# ECU-CAN-Adapter_Verteilte_Systeme_27_09_.net
KiCad netlist of a schematic drawn in EAGLE
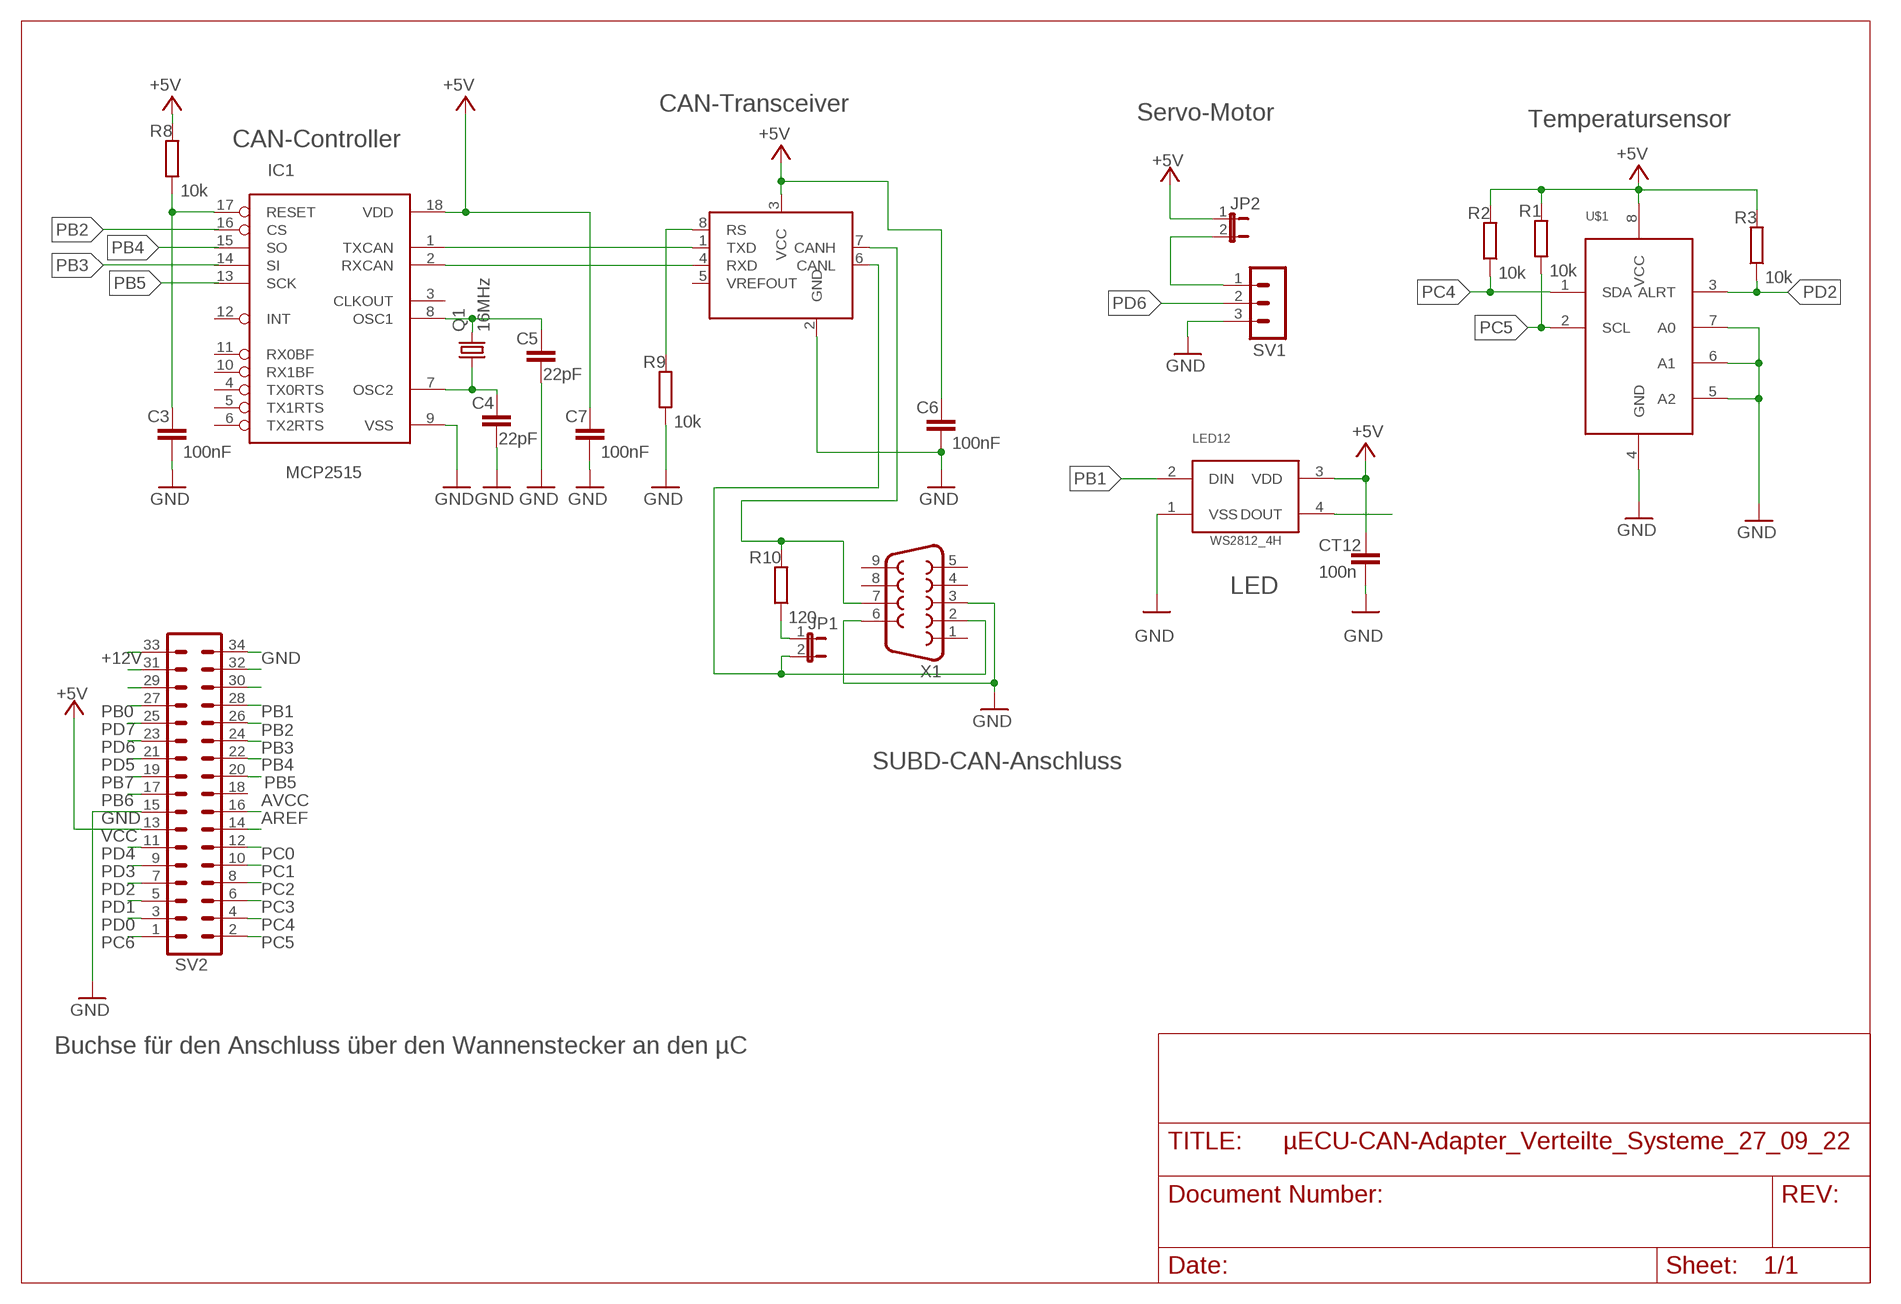
[diagram p0: schematic, sheet 1]

(export (version "E")
  (design (tool "Eeschema 10.0.6"))
  (components
    (comp (ref "C3")
      (value "100nF")
      (footprint "eagle-import:C0805K")
      (libsource (lib "eagle-import") (part "C-EUC0805K"))
    )
    (comp (ref "C4")
      (value "22pF")
      (footprint "eagle-import:C0805K")
      (libsource (lib "eagle-import") (part "C-EUC0805K"))
    )
    (comp (ref "C5")
      (value "22pF")
      (footprint "eagle-import:C0805K")
      (libsource (lib "eagle-import") (part "C-EUC0805K"))
    )
    (comp (ref "C6")
      (value "100nF")
      (footprint "eagle-import:C0805K")
      (libsource (lib "eagle-import") (part "C-EUC0805K"))
    )
    (comp (ref "C7")
      (value "100nF")
      (footprint "eagle-import:C0805K")
      (libsource (lib "eagle-import") (part "C-EUC0805K"))
    )
    (comp (ref "CT12")
      (value "100n")
      (footprint "eagle-import:C0805")
      (libsource (lib "eagle-import") (part "C-EUC0805"))
    )
    (comp (ref "IC1")
      (value "MCP2515")
      (footprint "eagle-import:SO-18DW")
      (libsource (lib "eagle-import") (part "MCP2515"))
    )
    (comp (ref "IC2")
      (value "PCA82C251")
      (footprint "eagle-import:SO8")
      (libsource (lib "eagle-import") (part "82C250SMDSMD"))
    )
    (comp (ref "JP1")
      (value "JP1E")
      (footprint "eagle-import:JP1")
      (libsource (lib "eagle-import") (part "JP1E"))
    )
    (comp (ref "JP2")
      (value "JP1E")
      (footprint "eagle-import:JP1")
      (libsource (lib "eagle-import") (part "JP1E"))
    )
    (comp (ref "LED12")
      (value "WS2812_4H")
      (footprint "eagle-import:WS2812_4")
      (libsource (lib "eagle-import") (part "WS2812_4H"))
    )
    (comp (ref "Q1")
      (value "16MHz")
      (footprint "eagle-import:HC49_S")
      (libsource (lib "eagle-import") (part "CRYSTALHC49S"))
    )
    (comp (ref "R1")
      (value "10k")
      (footprint "eagle-import:R0805")
      (libsource (lib "eagle-import") (part "R-EU_R0805"))
    )
    (comp (ref "R2")
      (value "10k")
      (footprint "eagle-import:R0805")
      (libsource (lib "eagle-import") (part "R-EU_R0805"))
    )
    (comp (ref "R3")
      (value "10k")
      (footprint "eagle-import:R0805")
      (libsource (lib "eagle-import") (part "R-EU_R0805"))
    )
    (comp (ref "R8")
      (value "10k")
      (footprint "eagle-import:R0805")
      (libsource (lib "eagle-import") (part "R-EU_R0805"))
    )
    (comp (ref "R9")
      (value "10k")
      (footprint "eagle-import:R0805")
      (libsource (lib "eagle-import") (part "R-EU_R0805"))
    )
    (comp (ref "R10")
      (value "120")
      (footprint "eagle-import:R0805")
      (libsource (lib "eagle-import") (part "R-EU_R0805"))
    )
    (comp (ref "SV1")
      (value "MA03-1")
      (footprint "eagle-import:MA03-1")
      (libsource (lib "eagle-import") (part "MA03-1"))
    )
    (comp (ref "SV2")
      (value "ML34")
      (footprint "eagle-import:ML34")
      (libsource (lib "eagle-import") (part "ML34"))
    )
    (comp (ref "U$1")
      (value "TMP75-SO8")
      (footprint "eagle-import:SO08")
      (libsource (lib "eagle-import") (part "TMP75-SO8"))
    )
    (comp (ref "X1")
      (value "F09HP")
      (footprint "eagle-import:F09HP")
      (libsource (lib "eagle-import") (part "F09HP"))
    )
  )
  (nets
    (net (code "1") (name "+5V") (class "Default")
      (node (ref "C6") (pin "1") (pinfunction "1_1") (pintype "passive"))
      (node (ref "C7") (pin "1") (pinfunction "1_1") (pintype "passive"))
      (node (ref "CT12") (pin "1") (pinfunction "1_1") (pintype "passive"))
      (node (ref "IC1") (pin "18") (pinfunction "VDD_18") (pintype "power_in"))
      (node (ref "IC2") (pin "3") (pinfunction "VCC_3") (pintype "power_in"))
      (node (ref "JP2") (pin "1") (pinfunction "1_1") (pintype "passive"))
      (node (ref "LED12") (pin "3") (pinfunction "VDD_3") (pintype "power_in"))
      (node (ref "R1") (pin "2") (pinfunction "2_2") (pintype "passive"))
      (node (ref "R2") (pin "2") (pinfunction "2_2") (pintype "passive"))
      (node (ref "R3") (pin "2") (pinfunction "2_2") (pintype "passive"))
      (node (ref "R8") (pin "2") (pinfunction "2_2") (pintype "passive"))
      (node (ref "SV2") (pin "13") (pinfunction "13_13") (pintype "passive"))
      (node (ref "U$1") (pin "8") (pinfunction "VCC_8") (pintype "power_in"))
    )
    (net (code "2") (name "/+12V") (class "Default")
      (node (ref "SV2") (pin "33") (pinfunction "33_33") (pintype "passive"))
    )
    (net (code "3") (name "/AREF") (class "Default")
      (node (ref "SV2") (pin "16") (pinfunction "16_16") (pintype "passive"))
    )
    (net (code "4") (name "/PB0") (class "Default")
      (node (ref "SV2") (pin "27") (pinfunction "27_27") (pintype "passive"))
    )
    (net (code "5") (name "/PB6") (class "Default")
      (node (ref "SV2") (pin "17") (pinfunction "17_17") (pintype "passive"))
    )
    (net (code "6") (name "/PB7") (class "Default")
      (node (ref "SV2") (pin "19") (pinfunction "19_19") (pintype "passive"))
    )
    (net (code "7") (name "/PC0") (class "Default")
      (node (ref "SV2") (pin "12") (pinfunction "12_12") (pintype "passive"))
    )
    (net (code "8") (name "/PC1") (class "Default")
      (node (ref "SV2") (pin "10") (pinfunction "10_10") (pintype "passive"))
    )
    (net (code "9") (name "/PC2") (class "Default")
      (node (ref "SV2") (pin "8") (pinfunction "8_8") (pintype "passive"))
    )
    (net (code "10") (name "/PC3") (class "Default")
      (node (ref "SV2") (pin "6") (pinfunction "6_6") (pintype "passive"))
    )
    (net (code "11") (name "/PC6") (class "Default")
      (node (ref "SV2") (pin "1") (pinfunction "1_1") (pintype "passive"))
    )
    (net (code "12") (name "/PD0") (class "Default")
      (node (ref "SV2") (pin "3") (pinfunction "3_3") (pintype "passive"))
    )
    (net (code "13") (name "/PD1") (class "Default")
      (node (ref "SV2") (pin "5") (pinfunction "5_5") (pintype "passive"))
    )
    (net (code "14") (name "/PD3") (class "Default")
      (node (ref "SV2") (pin "9") (pinfunction "9_9") (pintype "passive"))
    )
    (net (code "15") (name "/PD4") (class "Default")
      (node (ref "SV2") (pin "11") (pinfunction "11_11") (pintype "passive"))
    )
    (net (code "16") (name "/PD5") (class "Default")
      (node (ref "SV2") (pin "21") (pinfunction "21_21") (pintype "passive"))
    )
    (net (code "17") (name "/PD7") (class "Default")
      (node (ref "SV2") (pin "25") (pinfunction "25_25") (pintype "passive"))
    )
    (net (code "18") (name "GND") (class "Default")
      (node (ref "C3") (pin "2") (pinfunction "2_2") (pintype "passive"))
      (node (ref "C4") (pin "2") (pinfunction "2_2") (pintype "passive"))
      (node (ref "C5") (pin "2") (pinfunction "2_2") (pintype "passive"))
      (node (ref "C6") (pin "2") (pinfunction "2_2") (pintype "passive"))
      (node (ref "C7") (pin "2") (pinfunction "2_2") (pintype "passive"))
      (node (ref "CT12") (pin "2") (pinfunction "2_2") (pintype "passive"))
      (node (ref "IC1") (pin "9") (pinfunction "VSS_9") (pintype "power_in"))
      (node (ref "IC2") (pin "2") (pinfunction "GND_2") (pintype "power_in"))
      (node (ref "LED12") (pin "1") (pinfunction "VSS_1") (pintype "power_in"))
      (node (ref "R9") (pin "1") (pinfunction "1_1") (pintype "passive"))
      (node (ref "SV1") (pin "3") (pinfunction "3_3") (pintype "passive"))
      (node (ref "SV2") (pin "15") (pinfunction "15_15") (pintype "passive"))
      (node (ref "SV2") (pin "34") (pinfunction "34_34") (pintype "passive"))
      (node (ref "U$1") (pin "4") (pinfunction "GND_4") (pintype "power_in"))
      (node (ref "U$1") (pin "5") (pinfunction "A2_5") (pintype "input"))
      (node (ref "U$1") (pin "6") (pinfunction "A1_6") (pintype "input"))
      (node (ref "U$1") (pin "7") (pinfunction "A0_7") (pintype "input"))
      (node (ref "X1") (pin "3") (pinfunction "3_3") (pintype "passive"))
      (node (ref "X1") (pin "6") (pinfunction "6_6") (pintype "passive"))
    )
    (net (code "19") (name "Net-(IC1-OSC1)") (class "Default")
      (node (ref "C5") (pin "1") (pinfunction "1_1") (pintype "passive"))
      (node (ref "IC1") (pin "8") (pinfunction "OSC1_8") (pintype "input"))
      (node (ref "Q1") (pin "2") (pinfunction "2_2") (pintype "passive"))
    )
    (net (code "20") (name "Net-(IC1-OSC2)") (class "Default")
      (node (ref "C4") (pin "1") (pinfunction "1_1") (pintype "passive"))
      (node (ref "IC1") (pin "7") (pinfunction "OSC2_7") (pintype "input"))
      (node (ref "Q1") (pin "1") (pinfunction "1_1") (pintype "passive"))
    )
    (net (code "21") (name "Net-(IC1-RESET)") (class "Default")
      (node (ref "C3") (pin "1") (pinfunction "1_1") (pintype "passive"))
      (node (ref "IC1") (pin "17") (pinfunction "RESET_17") (pintype "input"))
      (node (ref "R8") (pin "1") (pinfunction "1_1") (pintype "passive"))
    )
    (net (code "22") (name "Net-(IC1-RXCAN)") (class "Default")
      (node (ref "IC1") (pin "2") (pinfunction "RXCAN_2") (pintype "input"))
      (node (ref "IC2") (pin "4") (pinfunction "RXD_4") (pintype "output"))
    )
    (net (code "23") (name "Net-(IC1-TXCAN)") (class "Default")
      (node (ref "IC1") (pin "1") (pinfunction "TXCAN_1") (pintype "output"))
      (node (ref "IC2") (pin "1") (pinfunction "TXD_1") (pintype "input"))
    )
    (net (code "24") (name "Net-(IC2-CANH)") (class "Default")
      (node (ref "IC2") (pin "7") (pinfunction "CANH_7") (pintype "bidirectional"))
      (node (ref "R10") (pin "2") (pinfunction "2_2") (pintype "passive"))
      (node (ref "X1") (pin "7") (pinfunction "7_7") (pintype "passive"))
    )
    (net (code "25") (name "Net-(IC2-CANL)") (class "Default")
      (node (ref "IC2") (pin "6") (pinfunction "CANL_6") (pintype "bidirectional"))
      (node (ref "JP1") (pin "2") (pinfunction "2_2") (pintype "passive"))
      (node (ref "X1") (pin "2") (pinfunction "2_2") (pintype "passive"))
    )
    (net (code "26") (name "Net-(IC2-RS)") (class "Default")
      (node (ref "IC2") (pin "8") (pinfunction "RS_8") (pintype "input"))
      (node (ref "R9") (pin "2") (pinfunction "2_2") (pintype "passive"))
    )
    (net (code "27") (name "Net-(JP1-Pad1)") (class "Default")
      (node (ref "JP1") (pin "1") (pinfunction "1_1") (pintype "passive"))
      (node (ref "R10") (pin "1") (pinfunction "1_1") (pintype "passive"))
    )
    (net (code "28") (name "Net-(JP2-Pad2)") (class "Default")
      (node (ref "JP2") (pin "2") (pinfunction "2_2") (pintype "passive"))
      (node (ref "SV1") (pin "1") (pinfunction "1_1") (pintype "passive"))
    )
    (net (code "29") (name "PB1") (class "Default")
      (node (ref "LED12") (pin "2") (pinfunction "DIN_2") (pintype "input"))
      (node (ref "SV2") (pin "28") (pinfunction "28_28") (pintype "passive"))
    )
    (net (code "30") (name "PB2") (class "Default")
      (node (ref "IC1") (pin "16") (pinfunction "CS_16") (pintype "input"))
      (node (ref "SV2") (pin "26") (pinfunction "26_26") (pintype "passive"))
    )
    (net (code "31") (name "PB3") (class "Default")
      (node (ref "IC1") (pin "14") (pinfunction "SI_14") (pintype "input"))
      (node (ref "SV2") (pin "24") (pinfunction "24_24") (pintype "passive"))
    )
    (net (code "32") (name "PB4") (class "Default")
      (node (ref "IC1") (pin "15") (pinfunction "SO_15") (pintype "output"))
      (node (ref "SV2") (pin "22") (pinfunction "22_22") (pintype "passive"))
    )
    (net (code "33") (name "PB5") (class "Default")
      (node (ref "IC1") (pin "13") (pinfunction "SCK_13") (pintype "input"))
      (node (ref "SV2") (pin "20") (pinfunction "20_20") (pintype "passive"))
    )
    (net (code "34") (name "PC4") (class "Default")
      (node (ref "R2") (pin "1") (pinfunction "1_1") (pintype "passive"))
      (node (ref "SV2") (pin "4") (pinfunction "4_4") (pintype "passive"))
      (node (ref "U$1") (pin "1") (pinfunction "SDA_1") (pintype "bidirectional"))
    )
    (net (code "35") (name "PC5") (class "Default")
      (node (ref "R1") (pin "1") (pinfunction "1_1") (pintype "passive"))
      (node (ref "SV2") (pin "2") (pinfunction "2_2") (pintype "passive"))
      (node (ref "U$1") (pin "2") (pinfunction "SCL_2") (pintype "input"))
    )
    (net (code "36") (name "PD2") (class "Default")
      (node (ref "R3") (pin "1") (pinfunction "1_1") (pintype "passive"))
      (node (ref "SV2") (pin "7") (pinfunction "7_7") (pintype "passive"))
      (node (ref "U$1") (pin "3") (pinfunction "ALRT_3") (pintype "output"))
    )
    (net (code "37") (name "PD6") (class "Default")
      (node (ref "SV1") (pin "2") (pinfunction "2_2") (pintype "passive"))
      (node (ref "SV2") (pin "23") (pinfunction "23_23") (pintype "passive"))
    )
    (net (code "38") (name "unconnected-(IC1-CLKOUT-Pad3)") (class "Default")
      (node (ref "IC1") (pin "3") (pinfunction "CLKOUT_3") (pintype "output"))
    )
    (net (code "39") (name "unconnected-(IC1-INT-Pad12)") (class "Default")
      (node (ref "IC1") (pin "12") (pinfunction "INT_12") (pintype "input"))
    )
    (net (code "40") (name "unconnected-(IC1-RX0BF-Pad11)") (class "Default")
      (node (ref "IC1") (pin "11") (pinfunction "RX0BF_11") (pintype "input"))
    )
    (net (code "41") (name "unconnected-(IC1-RX1BF-Pad10)") (class "Default")
      (node (ref "IC1") (pin "10") (pinfunction "RX1BF_10") (pintype "input"))
    )
    (net (code "42") (name "unconnected-(IC1-TX0RTS-Pad4)") (class "Default")
      (node (ref "IC1") (pin "4") (pinfunction "TX0RTS_4") (pintype "output"))
    )
    (net (code "43") (name "unconnected-(IC1-TX1RTS-Pad5)") (class "Default")
      (node (ref "IC1") (pin "5") (pinfunction "TX1RTS_5") (pintype "output"))
    )
    (net (code "44") (name "unconnected-(IC1-TX2RTS-Pad6)") (class "Default")
      (node (ref "IC1") (pin "6") (pinfunction "TX2RTS_6") (pintype "output"))
    )
    (net (code "45") (name "unconnected-(IC2-VREFOUT-Pad5)") (class "Default")
      (node (ref "IC2") (pin "5") (pinfunction "VREFOUT_5") (pintype "output"))
    )
    (net (code "46") (name "unconnected-(LED12-DOUT-Pad4)") (class "Default")
      (node (ref "LED12") (pin "4") (pinfunction "DOUT_4") (pintype "output"))
    )
    (net (code "47") (name "unconnected-(SV2-Pad14)") (class "Default")
      (node (ref "SV2") (pin "14") (pinfunction "14_14") (pintype "passive"))
    )
    (net (code "48") (name "unconnected-(SV2-Pad18)") (class "Default")
      (node (ref "SV2") (pin "18") (pinfunction "18_18") (pintype "passive"))
    )
    (net (code "49") (name "unconnected-(SV2-Pad29)") (class "Default")
      (node (ref "SV2") (pin "29") (pinfunction "29_29") (pintype "passive"))
    )
    (net (code "50") (name "unconnected-(SV2-Pad30)") (class "Default")
      (node (ref "SV2") (pin "30") (pinfunction "30_30") (pintype "passive"))
    )
    (net (code "51") (name "unconnected-(SV2-Pad31)") (class "Default")
      (node (ref "SV2") (pin "31") (pinfunction "31_31") (pintype "passive"))
    )
    (net (code "52") (name "unconnected-(SV2-Pad32)") (class "Default")
      (node (ref "SV2") (pin "32") (pinfunction "32_32") (pintype "passive"))
    )
    (net (code "53") (name "unconnected-(X1-Pad1)") (class "Default")
      (node (ref "X1") (pin "1") (pinfunction "1_1") (pintype "passive"))
    )
    (net (code "54") (name "unconnected-(X1-Pad4)") (class "Default")
      (node (ref "X1") (pin "4") (pinfunction "4_4") (pintype "passive"))
    )
    (net (code "55") (name "unconnected-(X1-Pad5)") (class "Default")
      (node (ref "X1") (pin "5") (pinfunction "5_5") (pintype "passive"))
    )
    (net (code "56") (name "unconnected-(X1-Pad8)") (class "Default")
      (node (ref "X1") (pin "8") (pinfunction "8_8") (pintype "passive"))
    )
    (net (code "57") (name "unconnected-(X1-Pad9)") (class "Default")
      (node (ref "X1") (pin "9") (pinfunction "9_9") (pintype "passive"))
    )
  )
)
